# RPi_DAQ_Hat_MCU.net
KiCad netlist of a schematic drawn in Altium Designer
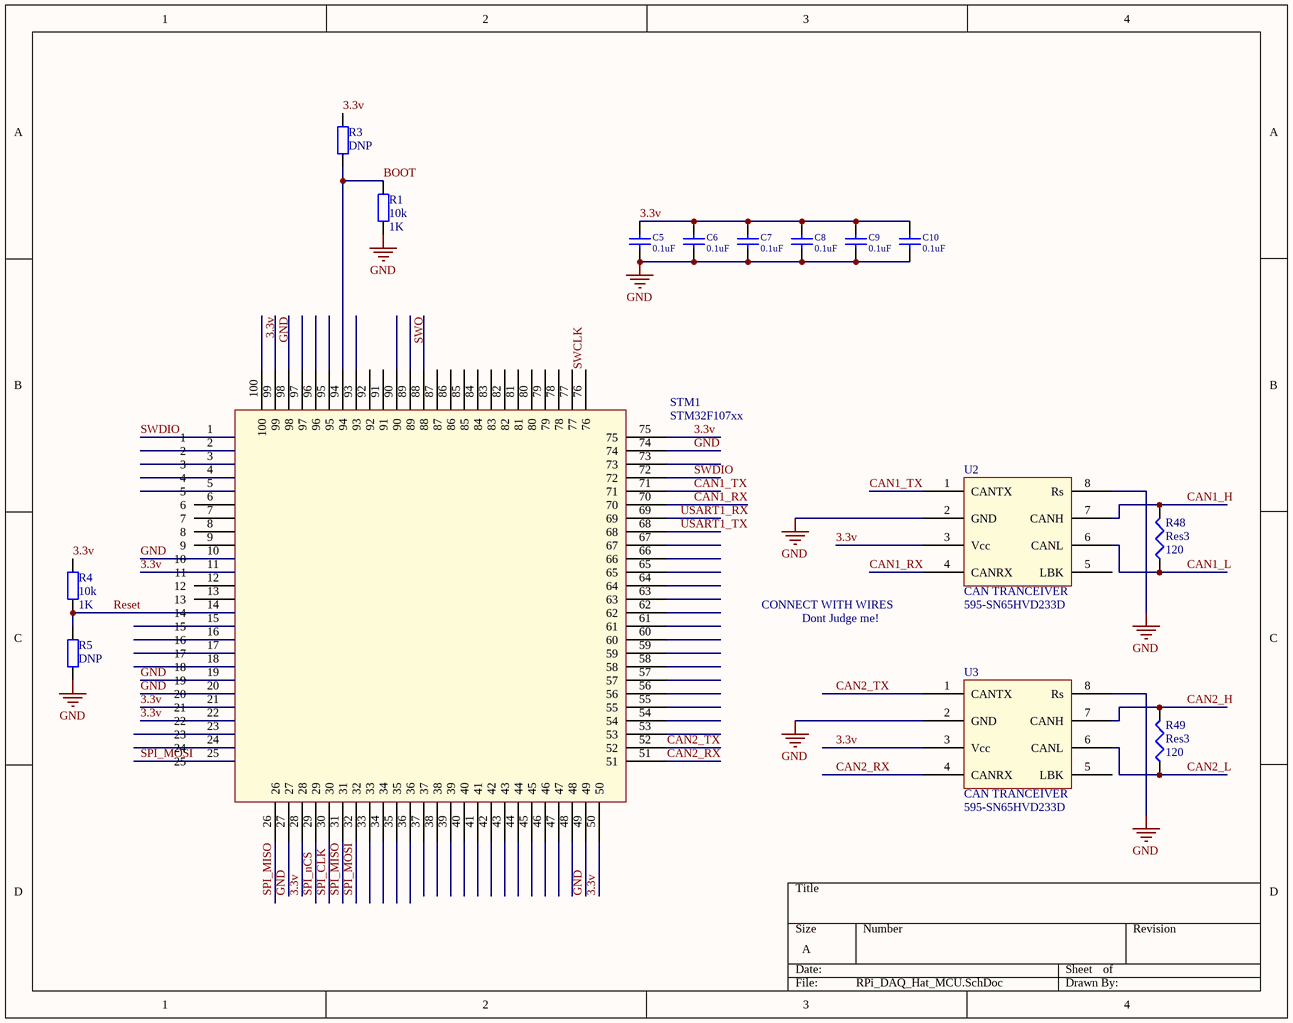
[diagram p0: RPi_DAQ_Hat_MCU.SchDoc]

(export (version "E")
  (design (tool "Eeschema 10.0.6"))
  (components
    (comp (ref "C5")
      (value "0.1uF")
      (footprint "R0805")
      (description "Capacitor")
      (libsource (lib "SpiritLevel_2E") (part "CAP_1"))
    )
    (comp (ref "C6")
      (value "0.1uF")
      (footprint "R0805")
      (description "Capacitor")
      (libsource (lib "SpiritLevel_2E") (part "CAP_1"))
    )
    (comp (ref "C7")
      (value "0.1uF")
      (footprint "R0805")
      (description "Capacitor")
      (libsource (lib "SpiritLevel_2E") (part "CAP_1"))
    )
    (comp (ref "C8")
      (value "0.1uF")
      (footprint "R0805")
      (description "Capacitor")
      (libsource (lib "SpiritLevel_2E") (part "CAP_1"))
    )
    (comp (ref "C9")
      (value "0.1uF")
      (footprint "R0805")
      (description "Capacitor")
      (libsource (lib "SpiritLevel_2E") (part "CAP_1"))
    )
    (comp (ref "C10")
      (value "0.1uF")
      (footprint "R0805")
      (description "Capacitor")
      (libsource (lib "SpiritLevel_2E") (part "CAP_1"))
    )
    (comp (ref "R1")
      (value "10k")
      (footprint "R0805")
      (description "Resistor")
      (fields (field (name "ALTIUM_VALUE") "1K") (field (name "PUBLISHER") "Altium Limited"))
      (libsource (lib "Miscellaneous Devices") (part "Res2"))
    )
    (comp (ref "R3")
      (value "DNP")
      (footprint "R0805")
      (description "Resistor")
      (fields (field (name "PUBLISHER") "Altium Limited"))
      (libsource (lib "Miscellaneous Devices") (part "Res2"))
    )
    (comp (ref "R4")
      (value "10k")
      (footprint "R0805")
      (description "Resistor")
      (fields (field (name "ALTIUM_VALUE") "1K") (field (name "PUBLISHER") "Altium Limited"))
      (libsource (lib "Miscellaneous Devices") (part "Res2"))
    )
    (comp (ref "R5")
      (value "DNP")
      (footprint "R0805")
      (description "Resistor")
      (fields (field (name "PUBLISHER") "Altium Limited"))
      (libsource (lib "Miscellaneous Devices") (part "Res2"))
    )
    (comp (ref "R48")
      (value "Res3")
      (footprint "R0805")
      (description "Resistor")
      (fields (field (name "ALTIUM_VALUE") "120") (field (name "PUBLISHER") "Altium Limited"))
      (libsource (lib "Miscellaneous Devices") (part "Res3"))
    )
    (comp (ref "R49")
      (value "Res3")
      (footprint "R0805")
      (description "Resistor")
      (fields (field (name "ALTIUM_VALUE") "120") (field (name "PUBLISHER") "Altium Limited"))
      (libsource (lib "Miscellaneous Devices") (part "Res3"))
    )
    (comp (ref "STM1")
      (value "STM32F107xx")
      (footprint "LQFP100")
      (libsource (lib "STM32_1") (part "STM32F107xx"))
    )
    (comp (ref "U2")
      (value "CAN TRANCEIVER")
      (footprint "SOP8")
      (fields (field (name "SUPPLIER PART NUMBER 1") "595-SN65HVD233D"))
      (libsource (lib "CAN_Node") (part "595-SN65HVD233"))
    )
    (comp (ref "U3")
      (value "CAN TRANCEIVER")
      (footprint "SOP8")
      (fields (field (name "SUPPLIER PART NUMBER 1") "595-SN65HVD233D"))
      (libsource (lib "CAN_Node") (part "595-SN65HVD233"))
    )
  )
  (nets
    (net (code "1") (name "/3.3v") (class "Default")
      (node (ref "C10") (pin "1") (pinfunction "1_1") (pintype "passive"))
      (node (ref "C5") (pin "1") (pinfunction "1_1") (pintype "passive"))
      (node (ref "C6") (pin "1") (pinfunction "1_1") (pintype "passive"))
      (node (ref "C7") (pin "1") (pinfunction "1_1") (pintype "passive"))
      (node (ref "C8") (pin "1") (pinfunction "1_1") (pintype "passive"))
      (node (ref "C9") (pin "1") (pinfunction "1_1") (pintype "passive"))
      (node (ref "R3") (pin "2") (pinfunction "2_2") (pintype "passive"))
      (node (ref "R4") (pin "2") (pinfunction "2_2") (pintype "passive"))
      (node (ref "STM1") (pin "100") (pinfunction "100_100") (pintype "passive"))
      (node (ref "STM1") (pin "11") (pinfunction "11_11") (pintype "passive"))
      (node (ref "STM1") (pin "21") (pinfunction "21_21") (pintype "passive"))
      (node (ref "STM1") (pin "22") (pinfunction "22_22") (pintype "passive"))
      (node (ref "STM1") (pin "28") (pinfunction "28_28") (pintype "passive"))
      (node (ref "STM1") (pin "50") (pinfunction "50_50") (pintype "passive"))
      (node (ref "STM1") (pin "75") (pinfunction "75_75") (pintype "passive"))
      (node (ref "U2") (pin "3") (pinfunction "Vcc_3") (pintype "passive"))
      (node (ref "U3") (pin "3") (pinfunction "Vcc_3") (pintype "passive"))
    )
    (net (code "2") (name "/BOOT") (class "Default")
      (node (ref "R1") (pin "2") (pinfunction "2_2") (pintype "passive"))
      (node (ref "R3") (pin "1") (pinfunction "1_1") (pintype "passive"))
      (node (ref "STM1") (pin "94") (pinfunction "94_94") (pintype "passive"))
    )
    (net (code "3") (name "/CAN1_H") (class "Default")
      (node (ref "R48") (pin "2") (pinfunction "2_2") (pintype "passive"))
      (node (ref "U2") (pin "7") (pinfunction "CANH_7") (pintype "passive"))
    )
    (net (code "4") (name "/CAN1_L") (class "Default")
      (node (ref "R48") (pin "1") (pinfunction "1_1") (pintype "passive"))
      (node (ref "U2") (pin "6") (pinfunction "CANL_6") (pintype "passive"))
    )
    (net (code "5") (name "/CAN1_RX") (class "Default")
      (node (ref "STM1") (pin "70") (pinfunction "70_70") (pintype "passive"))
      (node (ref "U2") (pin "4") (pinfunction "CANRX_4") (pintype "passive"))
    )
    (net (code "6") (name "/CAN1_TX") (class "Default")
      (node (ref "STM1") (pin "71") (pinfunction "71_71") (pintype "passive"))
      (node (ref "U2") (pin "1") (pinfunction "CANTX_1") (pintype "passive"))
    )
    (net (code "7") (name "/CAN2_H") (class "Default")
      (node (ref "R49") (pin "2") (pinfunction "2_2") (pintype "passive"))
      (node (ref "U3") (pin "7") (pinfunction "CANH_7") (pintype "passive"))
    )
    (net (code "8") (name "/CAN2_L") (class "Default")
      (node (ref "R49") (pin "1") (pinfunction "1_1") (pintype "passive"))
      (node (ref "U3") (pin "6") (pinfunction "CANL_6") (pintype "passive"))
    )
    (net (code "9") (name "/CAN2_RX") (class "Default")
      (node (ref "STM1") (pin "51") (pinfunction "51_51") (pintype "passive"))
      (node (ref "U3") (pin "4") (pinfunction "CANRX_4") (pintype "passive"))
    )
    (net (code "10") (name "/CAN2_TX") (class "Default")
      (node (ref "STM1") (pin "52") (pinfunction "52_52") (pintype "passive"))
      (node (ref "U3") (pin "1") (pinfunction "CANTX_1") (pintype "passive"))
    )
    (net (code "11") (name "/Reset") (class "Default")
      (node (ref "R4") (pin "1") (pinfunction "1_1") (pintype "passive"))
      (node (ref "R5") (pin "2") (pinfunction "2_2") (pintype "passive"))
      (node (ref "STM1") (pin "14") (pinfunction "14_14") (pintype "passive"))
    )
    (net (code "12") (name "/SPI_CLK") (class "Default")
      (node (ref "STM1") (pin "30") (pinfunction "30_30") (pintype "passive"))
    )
    (net (code "13") (name "/SPI_MISO") (class "Default")
      (node (ref "STM1") (pin "26") (pinfunction "26_26") (pintype "passive"))
      (node (ref "STM1") (pin "31") (pinfunction "31_31") (pintype "passive"))
    )
    (net (code "14") (name "/SPI_MOSI") (class "Default")
      (node (ref "STM1") (pin "25") (pinfunction "25_25") (pintype "passive"))
      (node (ref "STM1") (pin "32") (pinfunction "32_32") (pintype "passive"))
    )
    (net (code "15") (name "/SPI_nCS") (class "Default")
      (node (ref "STM1") (pin "29") (pinfunction "29_29") (pintype "passive"))
    )
    (net (code "16") (name "/SWCLK") (class "Default")
      (node (ref "STM1") (pin "76") (pinfunction "76_76") (pintype "passive"))
    )
    (net (code "17") (name "/SWDIO") (class "Default")
      (node (ref "STM1") (pin "1") (pinfunction "1_1") (pintype "passive"))
      (node (ref "STM1") (pin "72") (pinfunction "72_72") (pintype "passive"))
    )
    (net (code "18") (name "/SWO") (class "Default")
      (node (ref "STM1") (pin "89") (pinfunction "89_89") (pintype "passive"))
    )
    (net (code "19") (name "/USART1_RX") (class "Default")
      (node (ref "STM1") (pin "69") (pinfunction "69_69") (pintype "passive"))
    )
    (net (code "20") (name "/USART1_TX") (class "Default")
      (node (ref "STM1") (pin "68") (pinfunction "68_68") (pintype "passive"))
    )
    (net (code "21") (name "GND") (class "Default")
      (node (ref "C10") (pin "2") (pinfunction "2_2") (pintype "passive"))
      (node (ref "C5") (pin "2") (pinfunction "2_2") (pintype "passive"))
      (node (ref "C6") (pin "2") (pinfunction "2_2") (pintype "passive"))
      (node (ref "C7") (pin "2") (pinfunction "2_2") (pintype "passive"))
      (node (ref "C8") (pin "2") (pinfunction "2_2") (pintype "passive"))
      (node (ref "C9") (pin "2") (pinfunction "2_2") (pintype "passive"))
      (node (ref "R1") (pin "1") (pinfunction "1_1") (pintype "passive"))
      (node (ref "R5") (pin "1") (pinfunction "1_1") (pintype "passive"))
      (node (ref "STM1") (pin "10") (pinfunction "10_10") (pintype "passive"))
      (node (ref "STM1") (pin "19") (pinfunction "19_19") (pintype "passive"))
      (node (ref "STM1") (pin "20") (pinfunction "20_20") (pintype "passive"))
      (node (ref "STM1") (pin "27") (pinfunction "27_27") (pintype "passive"))
      (node (ref "STM1") (pin "49") (pinfunction "49_49") (pintype "passive"))
      (node (ref "STM1") (pin "74") (pinfunction "74_74") (pintype "passive"))
      (node (ref "STM1") (pin "99") (pinfunction "99_99") (pintype "passive"))
      (node (ref "U2") (pin "2") (pinfunction "GND_2") (pintype "passive"))
      (node (ref "U2") (pin "8") (pinfunction "Rs_8") (pintype "passive"))
      (node (ref "U3") (pin "2") (pinfunction "GND_2") (pintype "passive"))
      (node (ref "U3") (pin "8") (pinfunction "Rs_8") (pintype "passive"))
    )
    (net (code "22") (name "unconnected-(STM1-Pad2)") (class "Default")
      (node (ref "STM1") (pin "2") (pinfunction "2_2") (pintype "passive"))
    )
    (net (code "23") (name "unconnected-(STM1-Pad3)") (class "Default")
      (node (ref "STM1") (pin "3") (pinfunction "3_3") (pintype "passive"))
    )
    (net (code "24") (name "unconnected-(STM1-Pad4)") (class "Default")
      (node (ref "STM1") (pin "4") (pinfunction "4_4") (pintype "passive"))
    )
    (net (code "25") (name "unconnected-(STM1-Pad5)") (class "Default")
      (node (ref "STM1") (pin "5") (pinfunction "5_5") (pintype "passive"))
    )
    (net (code "26") (name "unconnected-(STM1-Pad6)") (class "Default")
      (node (ref "STM1") (pin "6") (pinfunction "6_6") (pintype "passive"))
    )
    (net (code "27") (name "unconnected-(STM1-Pad7)") (class "Default")
      (node (ref "STM1") (pin "7") (pinfunction "7_7") (pintype "passive"))
    )
    (net (code "28") (name "unconnected-(STM1-Pad8)") (class "Default")
      (node (ref "STM1") (pin "8") (pinfunction "8_8") (pintype "passive"))
    )
    (net (code "29") (name "unconnected-(STM1-Pad9)") (class "Default")
      (node (ref "STM1") (pin "9") (pinfunction "9_9") (pintype "passive"))
    )
    (net (code "30") (name "unconnected-(STM1-Pad12)") (class "Default")
      (node (ref "STM1") (pin "12") (pinfunction "12_12") (pintype "passive"))
    )
    (net (code "31") (name "unconnected-(STM1-Pad13)") (class "Default")
      (node (ref "STM1") (pin "13") (pinfunction "13_13") (pintype "passive"))
    )
    (net (code "32") (name "unconnected-(STM1-Pad15)") (class "Default")
      (node (ref "STM1") (pin "15") (pinfunction "15_15") (pintype "passive"))
    )
    (net (code "33") (name "unconnected-(STM1-Pad16)") (class "Default")
      (node (ref "STM1") (pin "16") (pinfunction "16_16") (pintype "passive"))
    )
    (net (code "34") (name "unconnected-(STM1-Pad17)") (class "Default")
      (node (ref "STM1") (pin "17") (pinfunction "17_17") (pintype "passive"))
    )
    (net (code "35") (name "unconnected-(STM1-Pad18)") (class "Default")
      (node (ref "STM1") (pin "18") (pinfunction "18_18") (pintype "passive"))
    )
    (net (code "36") (name "unconnected-(STM1-Pad23)") (class "Default")
      (node (ref "STM1") (pin "23") (pinfunction "23_23") (pintype "passive"))
    )
    (net (code "37") (name "unconnected-(STM1-Pad24)") (class "Default")
      (node (ref "STM1") (pin "24") (pinfunction "24_24") (pintype "passive"))
    )
    (net (code "38") (name "unconnected-(STM1-Pad33)") (class "Default")
      (node (ref "STM1") (pin "33") (pinfunction "33_33") (pintype "passive"))
    )
    (net (code "39") (name "unconnected-(STM1-Pad34)") (class "Default")
      (node (ref "STM1") (pin "34") (pinfunction "34_34") (pintype "passive"))
    )
    (net (code "40") (name "unconnected-(STM1-Pad35)") (class "Default")
      (node (ref "STM1") (pin "35") (pinfunction "35_35") (pintype "passive"))
    )
    (net (code "41") (name "unconnected-(STM1-Pad36)") (class "Default")
      (node (ref "STM1") (pin "36") (pinfunction "36_36") (pintype "passive"))
    )
    (net (code "42") (name "unconnected-(STM1-Pad37)") (class "Default")
      (node (ref "STM1") (pin "37") (pinfunction "37_37") (pintype "passive"))
    )
    (net (code "43") (name "unconnected-(STM1-Pad38)") (class "Default")
      (node (ref "STM1") (pin "38") (pinfunction "38_38") (pintype "passive"))
    )
    (net (code "44") (name "unconnected-(STM1-Pad39)") (class "Default")
      (node (ref "STM1") (pin "39") (pinfunction "39_39") (pintype "passive"))
    )
    (net (code "45") (name "unconnected-(STM1-Pad40)") (class "Default")
      (node (ref "STM1") (pin "40") (pinfunction "40_40") (pintype "passive"))
    )
    (net (code "46") (name "unconnected-(STM1-Pad41)") (class "Default")
      (node (ref "STM1") (pin "41") (pinfunction "41_41") (pintype "passive"))
    )
    (net (code "47") (name "unconnected-(STM1-Pad42)") (class "Default")
      (node (ref "STM1") (pin "42") (pinfunction "42_42") (pintype "passive"))
    )
    (net (code "48") (name "unconnected-(STM1-Pad43)") (class "Default")
      (node (ref "STM1") (pin "43") (pinfunction "43_43") (pintype "passive"))
    )
    (net (code "49") (name "unconnected-(STM1-Pad44)") (class "Default")
      (node (ref "STM1") (pin "44") (pinfunction "44_44") (pintype "passive"))
    )
    (net (code "50") (name "unconnected-(STM1-Pad45)") (class "Default")
      (node (ref "STM1") (pin "45") (pinfunction "45_45") (pintype "passive"))
    )
    (net (code "51") (name "unconnected-(STM1-Pad46)") (class "Default")
      (node (ref "STM1") (pin "46") (pinfunction "46_46") (pintype "passive"))
    )
    (net (code "52") (name "unconnected-(STM1-Pad47)") (class "Default")
      (node (ref "STM1") (pin "47") (pinfunction "47_47") (pintype "passive"))
    )
    (net (code "53") (name "unconnected-(STM1-Pad48)") (class "Default")
      (node (ref "STM1") (pin "48") (pinfunction "48_48") (pintype "passive"))
    )
    (net (code "54") (name "unconnected-(STM1-Pad53)") (class "Default")
      (node (ref "STM1") (pin "53") (pinfunction "53_53") (pintype "passive"))
    )
    (net (code "55") (name "unconnected-(STM1-Pad54)") (class "Default")
      (node (ref "STM1") (pin "54") (pinfunction "54_54") (pintype "passive"))
    )
    (net (code "56") (name "unconnected-(STM1-Pad55)") (class "Default")
      (node (ref "STM1") (pin "55") (pinfunction "55_55") (pintype "passive"))
    )
    (net (code "57") (name "unconnected-(STM1-Pad56)") (class "Default")
      (node (ref "STM1") (pin "56") (pinfunction "56_56") (pintype "passive"))
    )
    (net (code "58") (name "unconnected-(STM1-Pad57)") (class "Default")
      (node (ref "STM1") (pin "57") (pinfunction "57_57") (pintype "passive"))
    )
    (net (code "59") (name "unconnected-(STM1-Pad58)") (class "Default")
      (node (ref "STM1") (pin "58") (pinfunction "58_58") (pintype "passive"))
    )
    (net (code "60") (name "unconnected-(STM1-Pad59)") (class "Default")
      (node (ref "STM1") (pin "59") (pinfunction "59_59") (pintype "passive"))
    )
    (net (code "61") (name "unconnected-(STM1-Pad60)") (class "Default")
      (node (ref "STM1") (pin "60") (pinfunction "60_60") (pintype "passive"))
    )
    (net (code "62") (name "unconnected-(STM1-Pad61)") (class "Default")
      (node (ref "STM1") (pin "61") (pinfunction "61_61") (pintype "passive"))
    )
    (net (code "63") (name "unconnected-(STM1-Pad62)") (class "Default")
      (node (ref "STM1") (pin "62") (pinfunction "62_62") (pintype "passive"))
    )
    (net (code "64") (name "unconnected-(STM1-Pad63)") (class "Default")
      (node (ref "STM1") (pin "63") (pinfunction "63_63") (pintype "passive"))
    )
    (net (code "65") (name "unconnected-(STM1-Pad64)") (class "Default")
      (node (ref "STM1") (pin "64") (pinfunction "64_64") (pintype "passive"))
    )
    (net (code "66") (name "unconnected-(STM1-Pad65)") (class "Default")
      (node (ref "STM1") (pin "65") (pinfunction "65_65") (pintype "passive"))
    )
    (net (code "67") (name "unconnected-(STM1-Pad66)") (class "Default")
      (node (ref "STM1") (pin "66") (pinfunction "66_66") (pintype "passive"))
    )
    (net (code "68") (name "unconnected-(STM1-Pad67)") (class "Default")
      (node (ref "STM1") (pin "67") (pinfunction "67_67") (pintype "passive"))
    )
    (net (code "69") (name "unconnected-(STM1-Pad73)") (class "Default")
      (node (ref "STM1") (pin "73") (pinfunction "73_73") (pintype "passive"))
    )
    (net (code "70") (name "unconnected-(STM1-Pad77)") (class "Default")
      (node (ref "STM1") (pin "77") (pinfunction "77_77") (pintype "passive"))
    )
    (net (code "71") (name "unconnected-(STM1-Pad78)") (class "Default")
      (node (ref "STM1") (pin "78") (pinfunction "78_78") (pintype "passive"))
    )
    (net (code "72") (name "unconnected-(STM1-Pad79)") (class "Default")
      (node (ref "STM1") (pin "79") (pinfunction "79_79") (pintype "passive"))
    )
    (net (code "73") (name "unconnected-(STM1-Pad80)") (class "Default")
      (node (ref "STM1") (pin "80") (pinfunction "80_80") (pintype "passive"))
    )
    (net (code "74") (name "unconnected-(STM1-Pad81)") (class "Default")
      (node (ref "STM1") (pin "81") (pinfunction "81_81") (pintype "passive"))
    )
    (net (code "75") (name "unconnected-(STM1-Pad82)") (class "Default")
      (node (ref "STM1") (pin "82") (pinfunction "82_82") (pintype "passive"))
    )
    (net (code "76") (name "unconnected-(STM1-Pad83)") (class "Default")
      (node (ref "STM1") (pin "83") (pinfunction "83_83") (pintype "passive"))
    )
    (net (code "77") (name "unconnected-(STM1-Pad84)") (class "Default")
      (node (ref "STM1") (pin "84") (pinfunction "84_84") (pintype "passive"))
    )
    (net (code "78") (name "unconnected-(STM1-Pad85)") (class "Default")
      (node (ref "STM1") (pin "85") (pinfunction "85_85") (pintype "passive"))
    )
    (net (code "79") (name "unconnected-(STM1-Pad86)") (class "Default")
      (node (ref "STM1") (pin "86") (pinfunction "86_86") (pintype "passive"))
    )
    (net (code "80") (name "unconnected-(STM1-Pad87)") (class "Default")
      (node (ref "STM1") (pin "87") (pinfunction "87_87") (pintype "passive"))
    )
    (net (code "81") (name "unconnected-(STM1-Pad88)") (class "Default")
      (node (ref "STM1") (pin "88") (pinfunction "88_88") (pintype "passive"))
    )
    (net (code "82") (name "unconnected-(STM1-Pad90)") (class "Default")
      (node (ref "STM1") (pin "90") (pinfunction "90_90") (pintype "passive"))
    )
    (net (code "83") (name "unconnected-(STM1-Pad91)") (class "Default")
      (node (ref "STM1") (pin "91") (pinfunction "91_91") (pintype "passive"))
    )
    (net (code "84") (name "unconnected-(STM1-Pad92)") (class "Default")
      (node (ref "STM1") (pin "92") (pinfunction "92_92") (pintype "passive"))
    )
    (net (code "85") (name "unconnected-(STM1-Pad93)") (class "Default")
      (node (ref "STM1") (pin "93") (pinfunction "93_93") (pintype "passive"))
    )
    (net (code "86") (name "unconnected-(STM1-Pad95)") (class "Default")
      (node (ref "STM1") (pin "95") (pinfunction "95_95") (pintype "passive"))
    )
    (net (code "87") (name "unconnected-(STM1-Pad96)") (class "Default")
      (node (ref "STM1") (pin "96") (pinfunction "96_96") (pintype "passive"))
    )
    (net (code "88") (name "unconnected-(STM1-Pad97)") (class "Default")
      (node (ref "STM1") (pin "97") (pinfunction "97_97") (pintype "passive"))
    )
    (net (code "89") (name "unconnected-(STM1-Pad98)") (class "Default")
      (node (ref "STM1") (pin "98") (pinfunction "98_98") (pintype "passive"))
    )
    (net (code "90") (name "unconnected-(U2-LBK-Pad5)") (class "Default")
      (node (ref "U2") (pin "5") (pinfunction "LBK_5") (pintype "passive"))
    )
    (net (code "91") (name "unconnected-(U3-LBK-Pad5)") (class "Default")
      (node (ref "U3") (pin "5") (pinfunction "LBK_5") (pintype "passive"))
    )
  )
)
